# DCDC.net
KiCad netlist of a schematic drawn in Altium Designer
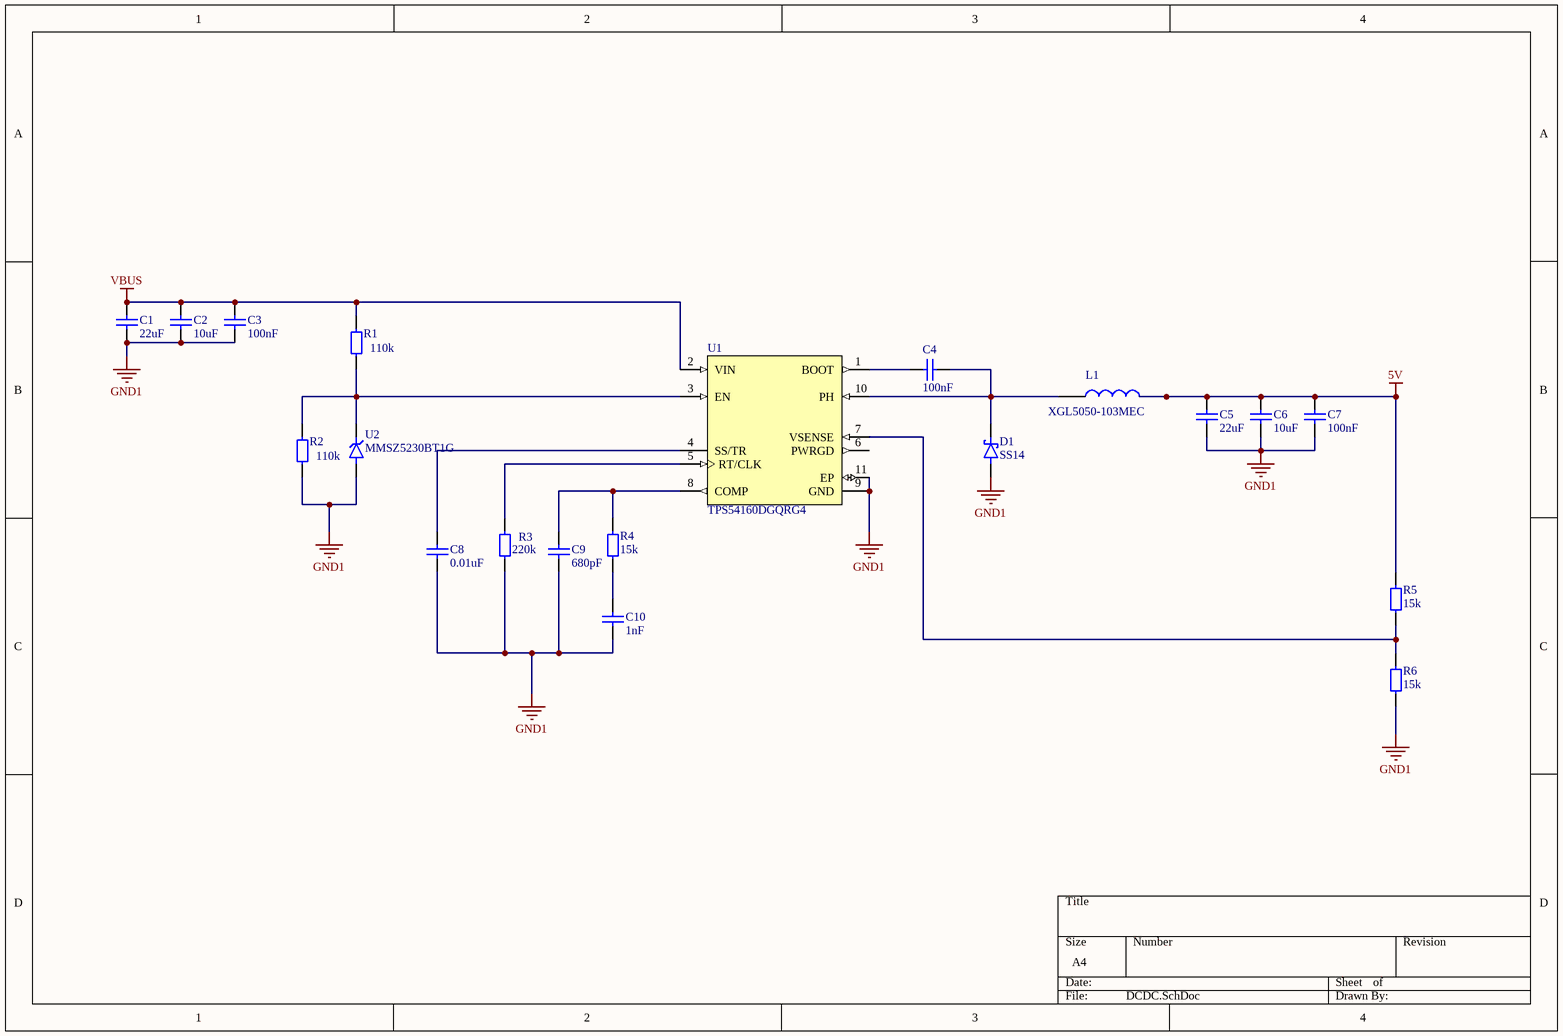
[diagram p0: DCDC.SchDoc]

(export (version "E")
  (design (tool "Eeschema 10.0.6"))
  (components
    (comp (ref "C1")
      (value "22uF")
      (footprint "1210_CAP")
      (description "22uF 50V 1210")
      (libsource (lib "Capacitor") (part "Capacitor 22uF 1210"))
    )
    (comp (ref "C2")
      (value "10uF")
      (footprint "0805_CAP")
      (description "10uF 50V 0805")
      (libsource (lib "Capacitor") (part "Capacitor 10uF 0805"))
    )
    (comp (ref "C3")
      (value "100nF")
      (footprint "0603 Capacitor")
      (description "100nF 50V 0603")
      (libsource (lib "Capacitor") (part "Capacitor 100nF 0603"))
    )
    (comp (ref "C4")
      (value "100nF")
      (footprint "0603 Capacitor")
      (description "100nF 50V 0603")
      (libsource (lib "Capacitor") (part "Capacitor 100nF 0603"))
    )
    (comp (ref "C5")
      (value "22uF")
      (footprint "1210_CAP")
      (description "22uF 50V 1210")
      (libsource (lib "Capacitor") (part "Capacitor 22uF 1210"))
    )
    (comp (ref "C6")
      (value "10uF")
      (footprint "0805_CAP")
      (description "10uF 50V 0805")
      (libsource (lib "Capacitor") (part "Capacitor 10uF 0805"))
    )
    (comp (ref "C7")
      (value "100nF")
      (footprint "0603 Capacitor")
      (description "100nF 50V 0603")
      (libsource (lib "Capacitor") (part "Capacitor 100nF 0603"))
    )
    (comp (ref "C8")
      (value "0.01uF")
      (footprint "0603 Capacitor")
      (description "100nF 50V 0603")
      (libsource (lib "Capacitor") (part "Capacitor 100nF 0603"))
    )
    (comp (ref "C9")
      (value "680pF")
      (footprint "0603 Capacitor")
      (description "100nF 50V 0603")
      (libsource (lib "Capacitor") (part "Capacitor 100nF 0603"))
    )
    (comp (ref "C10")
      (value "1nF")
      (footprint "0603 Capacitor")
      (description "100nF 50V 0603")
      (libsource (lib "Capacitor") (part "Capacitor 100nF 0603"))
    )
    (comp (ref "D1")
      (value "SS14")
      (footprint "DIOM4330X250N")
      (description "1A, 40V, Schottky Rectifier")
      (libsource (lib "Shared_Lib_V1") (part "SS14"))
    )
    (comp (ref "L1")
      (value "XGL5050-103MEC")
      (footprint "XGL5050")
      (description "10uH Shielded Molded Inductor 2.5 A")
      (fields (field (name "MANUFACTURER_PART_NUMBER") "XGL5050-153MEC"))
      (libsource (lib "Inductor") (part "XGL5050-103MEC"))
    )
    (comp (ref "R1")
      (value "110k")
      (footprint "0603 Resistor")
      (description "100k 0603")
      (libsource (lib "Resistors") (part "Resistor 100k 0603"))
    )
    (comp (ref "R2")
      (value "110k")
      (footprint "0603 Resistor")
      (description "100k 0603")
      (libsource (lib "Resistors") (part "Resistor 100k 0603"))
    )
    (comp (ref "R3")
      (value "220k")
      (footprint "0603 Resistor")
      (description "100k 0603")
      (libsource (lib "Resistors") (part "Resistor 100k 0603"))
    )
    (comp (ref "R4")
      (value "15k")
      (footprint "0603 Resistor")
      (description "100k 0603")
      (libsource (lib "Resistors") (part "Resistor 100k 0603"))
    )
    (comp (ref "R5")
      (value "15k")
      (footprint "0603 Resistor")
      (description "100k 0603")
      (libsource (lib "Resistors") (part "Resistor 100k 0603"))
    )
    (comp (ref "R6")
      (value "15k")
      (footprint "0603 Resistor")
      (description "100k 0603")
      (libsource (lib "Resistors") (part "Resistor 100k 0603"))
    )
    (comp (ref "U1")
      (value "TPS54160DGQRG4")
      (footprint "IC_XTR111AIDGQR")
      (description "3.5V to 60V Input, 1.5A Step-Down Converter with Eco-Mode 10-HVSSOP -40 to 150")
      (fields (field (name "MF") "Texas Instruments"))
      (libsource (lib "DCDC") (part "TPS54160DGQRG4"))
    )
    (comp (ref "U2")
      (value "MMSZ5230BT1G")
      (footprint "DIO_SZMMSZ5248CT1G")
      (description "Zener Diode 4.7V 500 mW ±2% Surface Mount SOD-123")
      (fields (field (name "MP") "SZMMSZ5248CT1G") (field (name "MF") "ON Semiconductor"))
      (libsource (lib "Shared_Lib_V1") (part "MMSZ5230BT1G"))
    )
  )
  (nets
    (net (code "1") (name "5V") (class "Default")
      (node (ref "C5") (pin "2") (pinfunction "2_2") (pintype "passive"))
      (node (ref "C6") (pin "2") (pinfunction "2_2") (pintype "passive"))
      (node (ref "C7") (pin "2") (pinfunction "2_2") (pintype "passive"))
      (node (ref "L1") (pin "2") (pinfunction "2_2") (pintype "passive"))
      (node (ref "R5") (pin "2") (pinfunction "CW_2") (pintype "passive"))
    )
    (net (code "2") (name "GND1") (class "Default")
      (node (ref "C1") (pin "1") (pinfunction "1_1") (pintype "passive"))
      (node (ref "C10") (pin "1") (pinfunction "1_1") (pintype "passive"))
      (node (ref "C2") (pin "1") (pinfunction "1_1") (pintype "passive"))
      (node (ref "C3") (pin "1") (pinfunction "1_1") (pintype "passive"))
      (node (ref "C5") (pin "1") (pinfunction "1_1") (pintype "passive"))
      (node (ref "C6") (pin "1") (pinfunction "1_1") (pintype "passive"))
      (node (ref "C7") (pin "1") (pinfunction "1_1") (pintype "passive"))
      (node (ref "C8") (pin "1") (pinfunction "1_1") (pintype "passive"))
      (node (ref "C9") (pin "1") (pinfunction "1_1") (pintype "passive"))
      (node (ref "D1") (pin "A") (pinfunction "A_A") (pintype "passive"))
      (node (ref "R2") (pin "1") (pinfunction "CCW_1") (pintype "passive"))
      (node (ref "R3") (pin "1") (pinfunction "CCW_1") (pintype "passive"))
      (node (ref "R6") (pin "1") (pinfunction "CCW_1") (pintype "passive"))
      (node (ref "U1") (pin "11") (pinfunction "EP_11") (pintype "bidirectional"))
      (node (ref "U1") (pin "9") (pinfunction "GND_9") (pintype "power_in"))
      (node (ref "U2") (pin "2") (pinfunction "A_2") (pintype "passive"))
    )
    (net (code "3") (name "Net-(D1-K)") (class "Default")
      (node (ref "C4") (pin "2") (pinfunction "2_2") (pintype "passive"))
      (node (ref "D1") (pin "C") (pinfunction "K_C") (pintype "passive"))
      (node (ref "L1") (pin "1") (pinfunction "1_1") (pintype "passive"))
      (node (ref "U1") (pin "10") (pinfunction "PH_10") (pintype "input"))
    )
    (net (code "4") (name "Net-(R1-CCW)") (class "Default")
      (node (ref "R1") (pin "1") (pinfunction "CCW_1") (pintype "passive"))
      (node (ref "R2") (pin "2") (pinfunction "CW_2") (pintype "passive"))
      (node (ref "U1") (pin "3") (pinfunction "EN_3") (pintype "input"))
      (node (ref "U2") (pin "1") (pinfunction "K_1") (pintype "passive"))
    )
    (net (code "5") (name "Net-(R3-CW)") (class "Default")
      (node (ref "R3") (pin "2") (pinfunction "CW_2") (pintype "passive"))
      (node (ref "U1") (pin "5") (pinfunction "RT/CLK_5") (pintype "input"))
    )
    (net (code "6") (name "Net-(R4-CCW)") (class "Default")
      (node (ref "C10") (pin "2") (pinfunction "2_2") (pintype "passive"))
      (node (ref "R4") (pin "1") (pinfunction "CCW_1") (pintype "passive"))
    )
    (net (code "7") (name "Net-(R4-CW)") (class "Default")
      (node (ref "C9") (pin "2") (pinfunction "2_2") (pintype "passive"))
      (node (ref "R4") (pin "2") (pinfunction "CW_2") (pintype "passive"))
      (node (ref "U1") (pin "8") (pinfunction "COMP_8") (pintype "output"))
    )
    (net (code "8") (name "Net-(R5-CCW)") (class "Default")
      (node (ref "R5") (pin "1") (pinfunction "CCW_1") (pintype "passive"))
      (node (ref "R6") (pin "2") (pinfunction "CW_2") (pintype "passive"))
      (node (ref "U1") (pin "7") (pinfunction "VSENSE_7") (pintype "input"))
    )
    (net (code "9") (name "Net-(U1-BOOT)") (class "Default")
      (node (ref "C4") (pin "1") (pinfunction "1_1") (pintype "passive"))
      (node (ref "U1") (pin "1") (pinfunction "BOOT_1") (pintype "output"))
    )
    (net (code "10") (name "Net-(U1-SS{slash}TR)") (class "Default")
      (node (ref "C8") (pin "2") (pinfunction "2_2") (pintype "passive"))
      (node (ref "U1") (pin "4") (pinfunction "SS/TR_4") (pintype "power_in"))
    )
    (net (code "11") (name "VBUS") (class "Default")
      (node (ref "C1") (pin "2") (pinfunction "2_2") (pintype "passive"))
      (node (ref "C2") (pin "2") (pinfunction "2_2") (pintype "passive"))
      (node (ref "C3") (pin "2") (pinfunction "2_2") (pintype "passive"))
      (node (ref "R1") (pin "2") (pinfunction "CW_2") (pintype "passive"))
      (node (ref "U1") (pin "2") (pinfunction "VIN_2") (pintype "input"))
    )
    (net (code "12") (name "unconnected-(U1-PWRGD-Pad6)") (class "Default")
      (node (ref "U1") (pin "6") (pinfunction "PWRGD_6") (pintype "output"))
    )
  )
)
